# pcb7.net
KiCad netlist of a schematic drawn in EAGLE
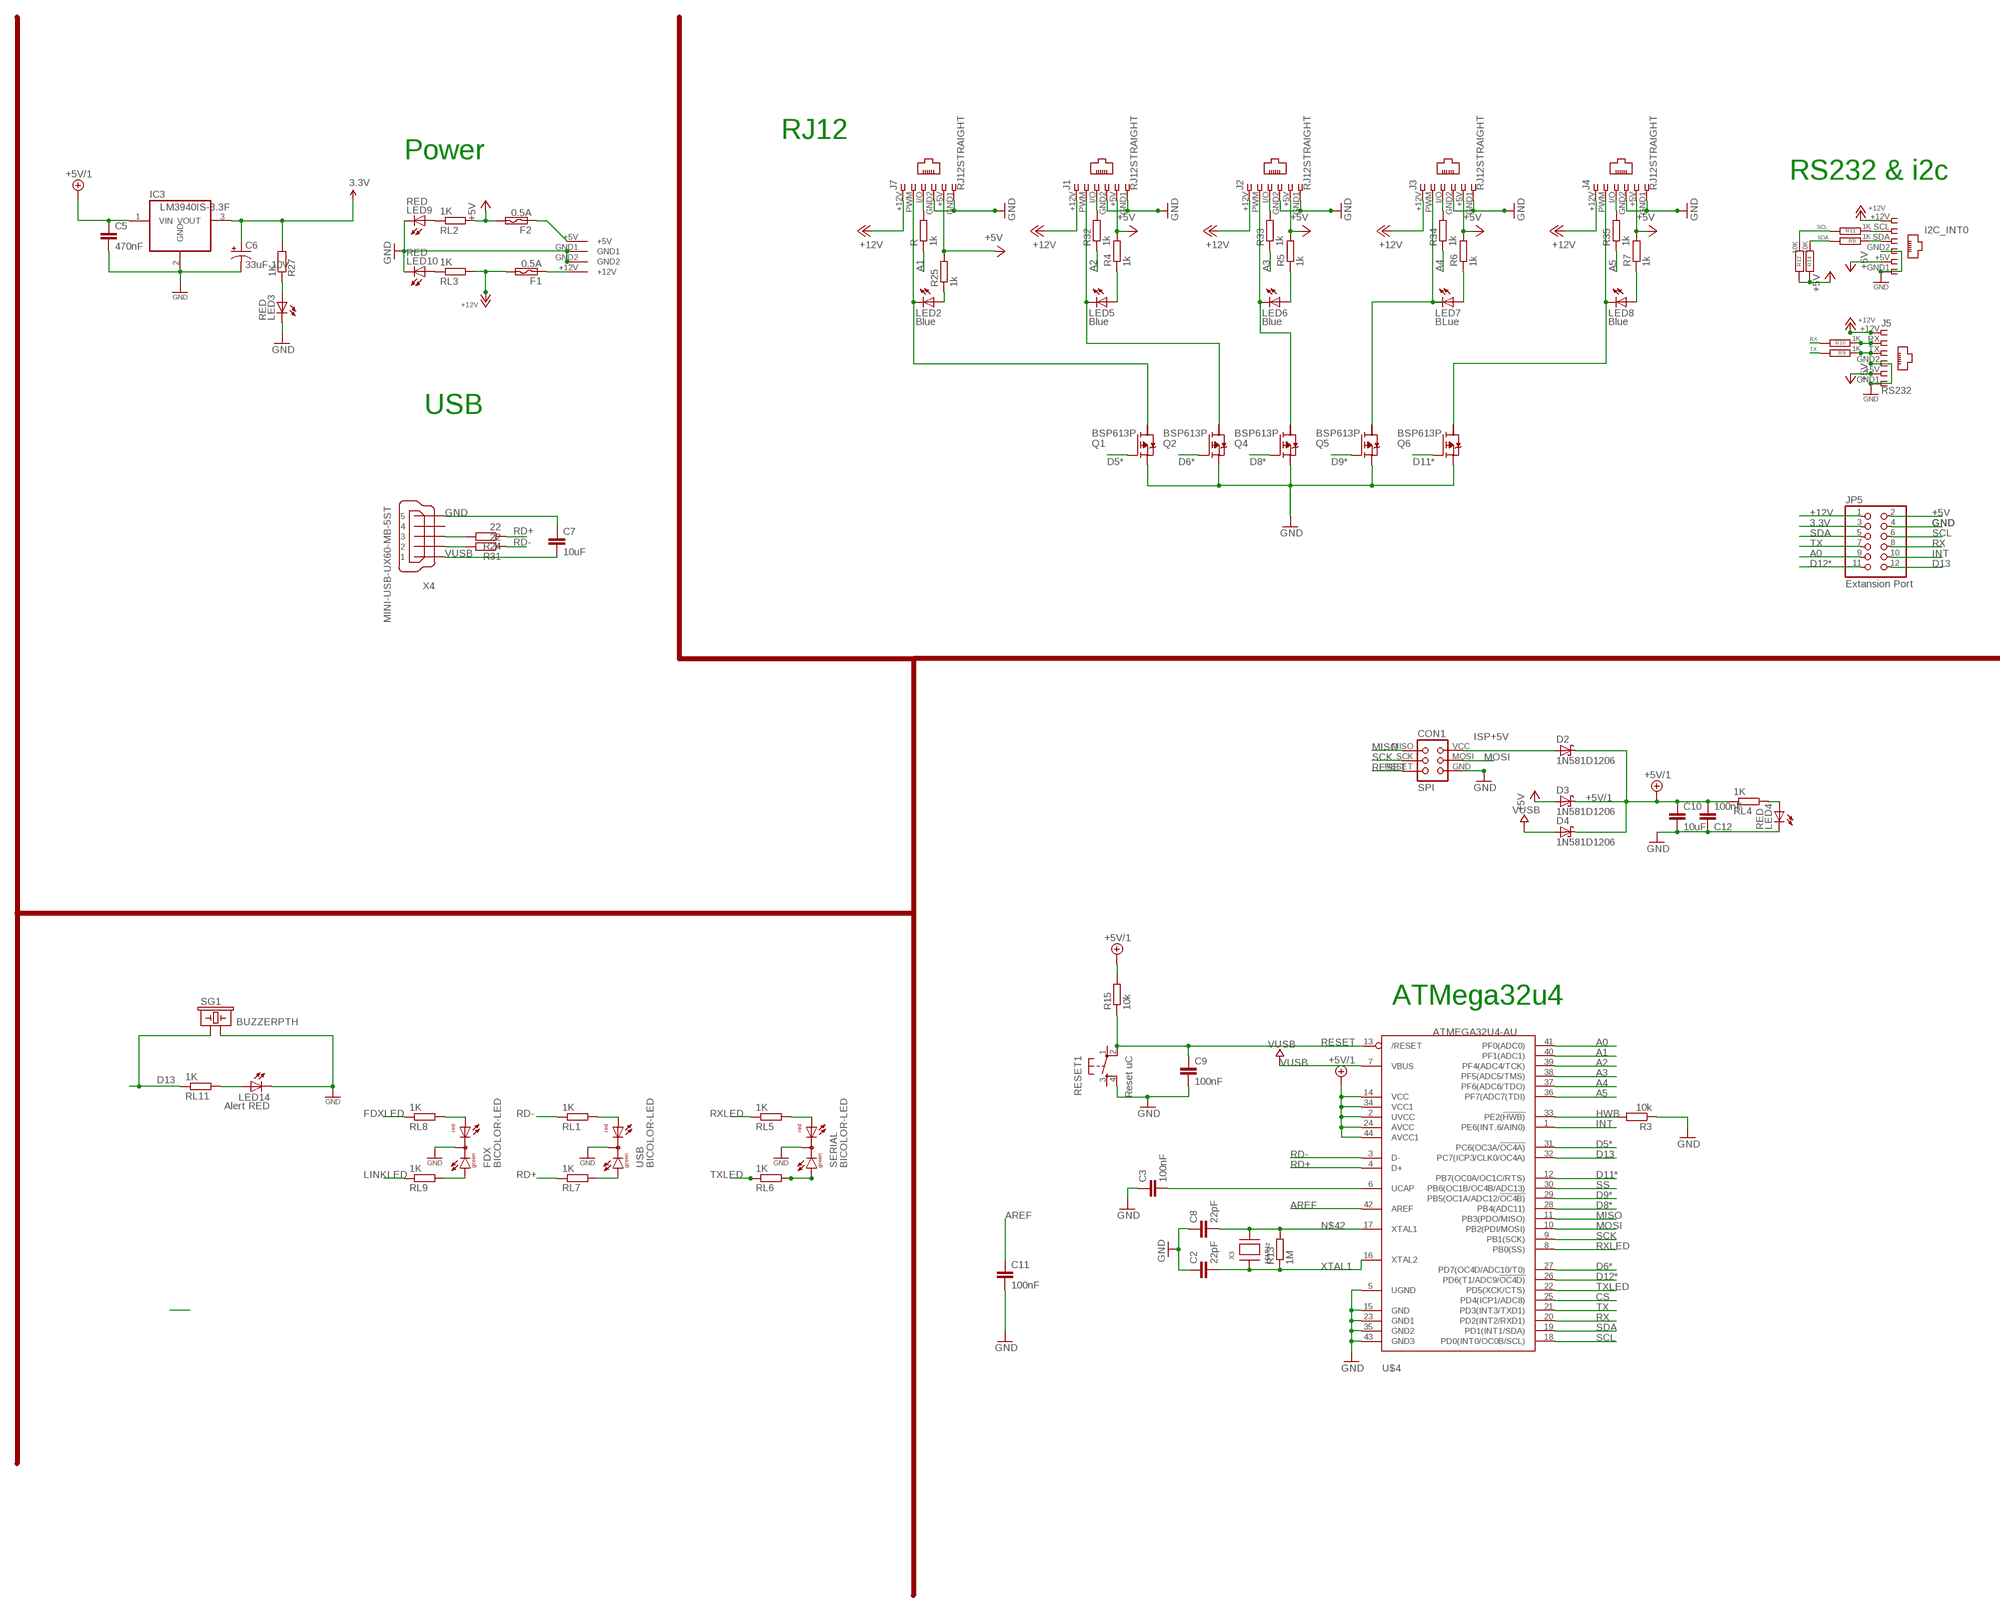
[diagram p0: schematic, sheet 1, part 1 of 2]
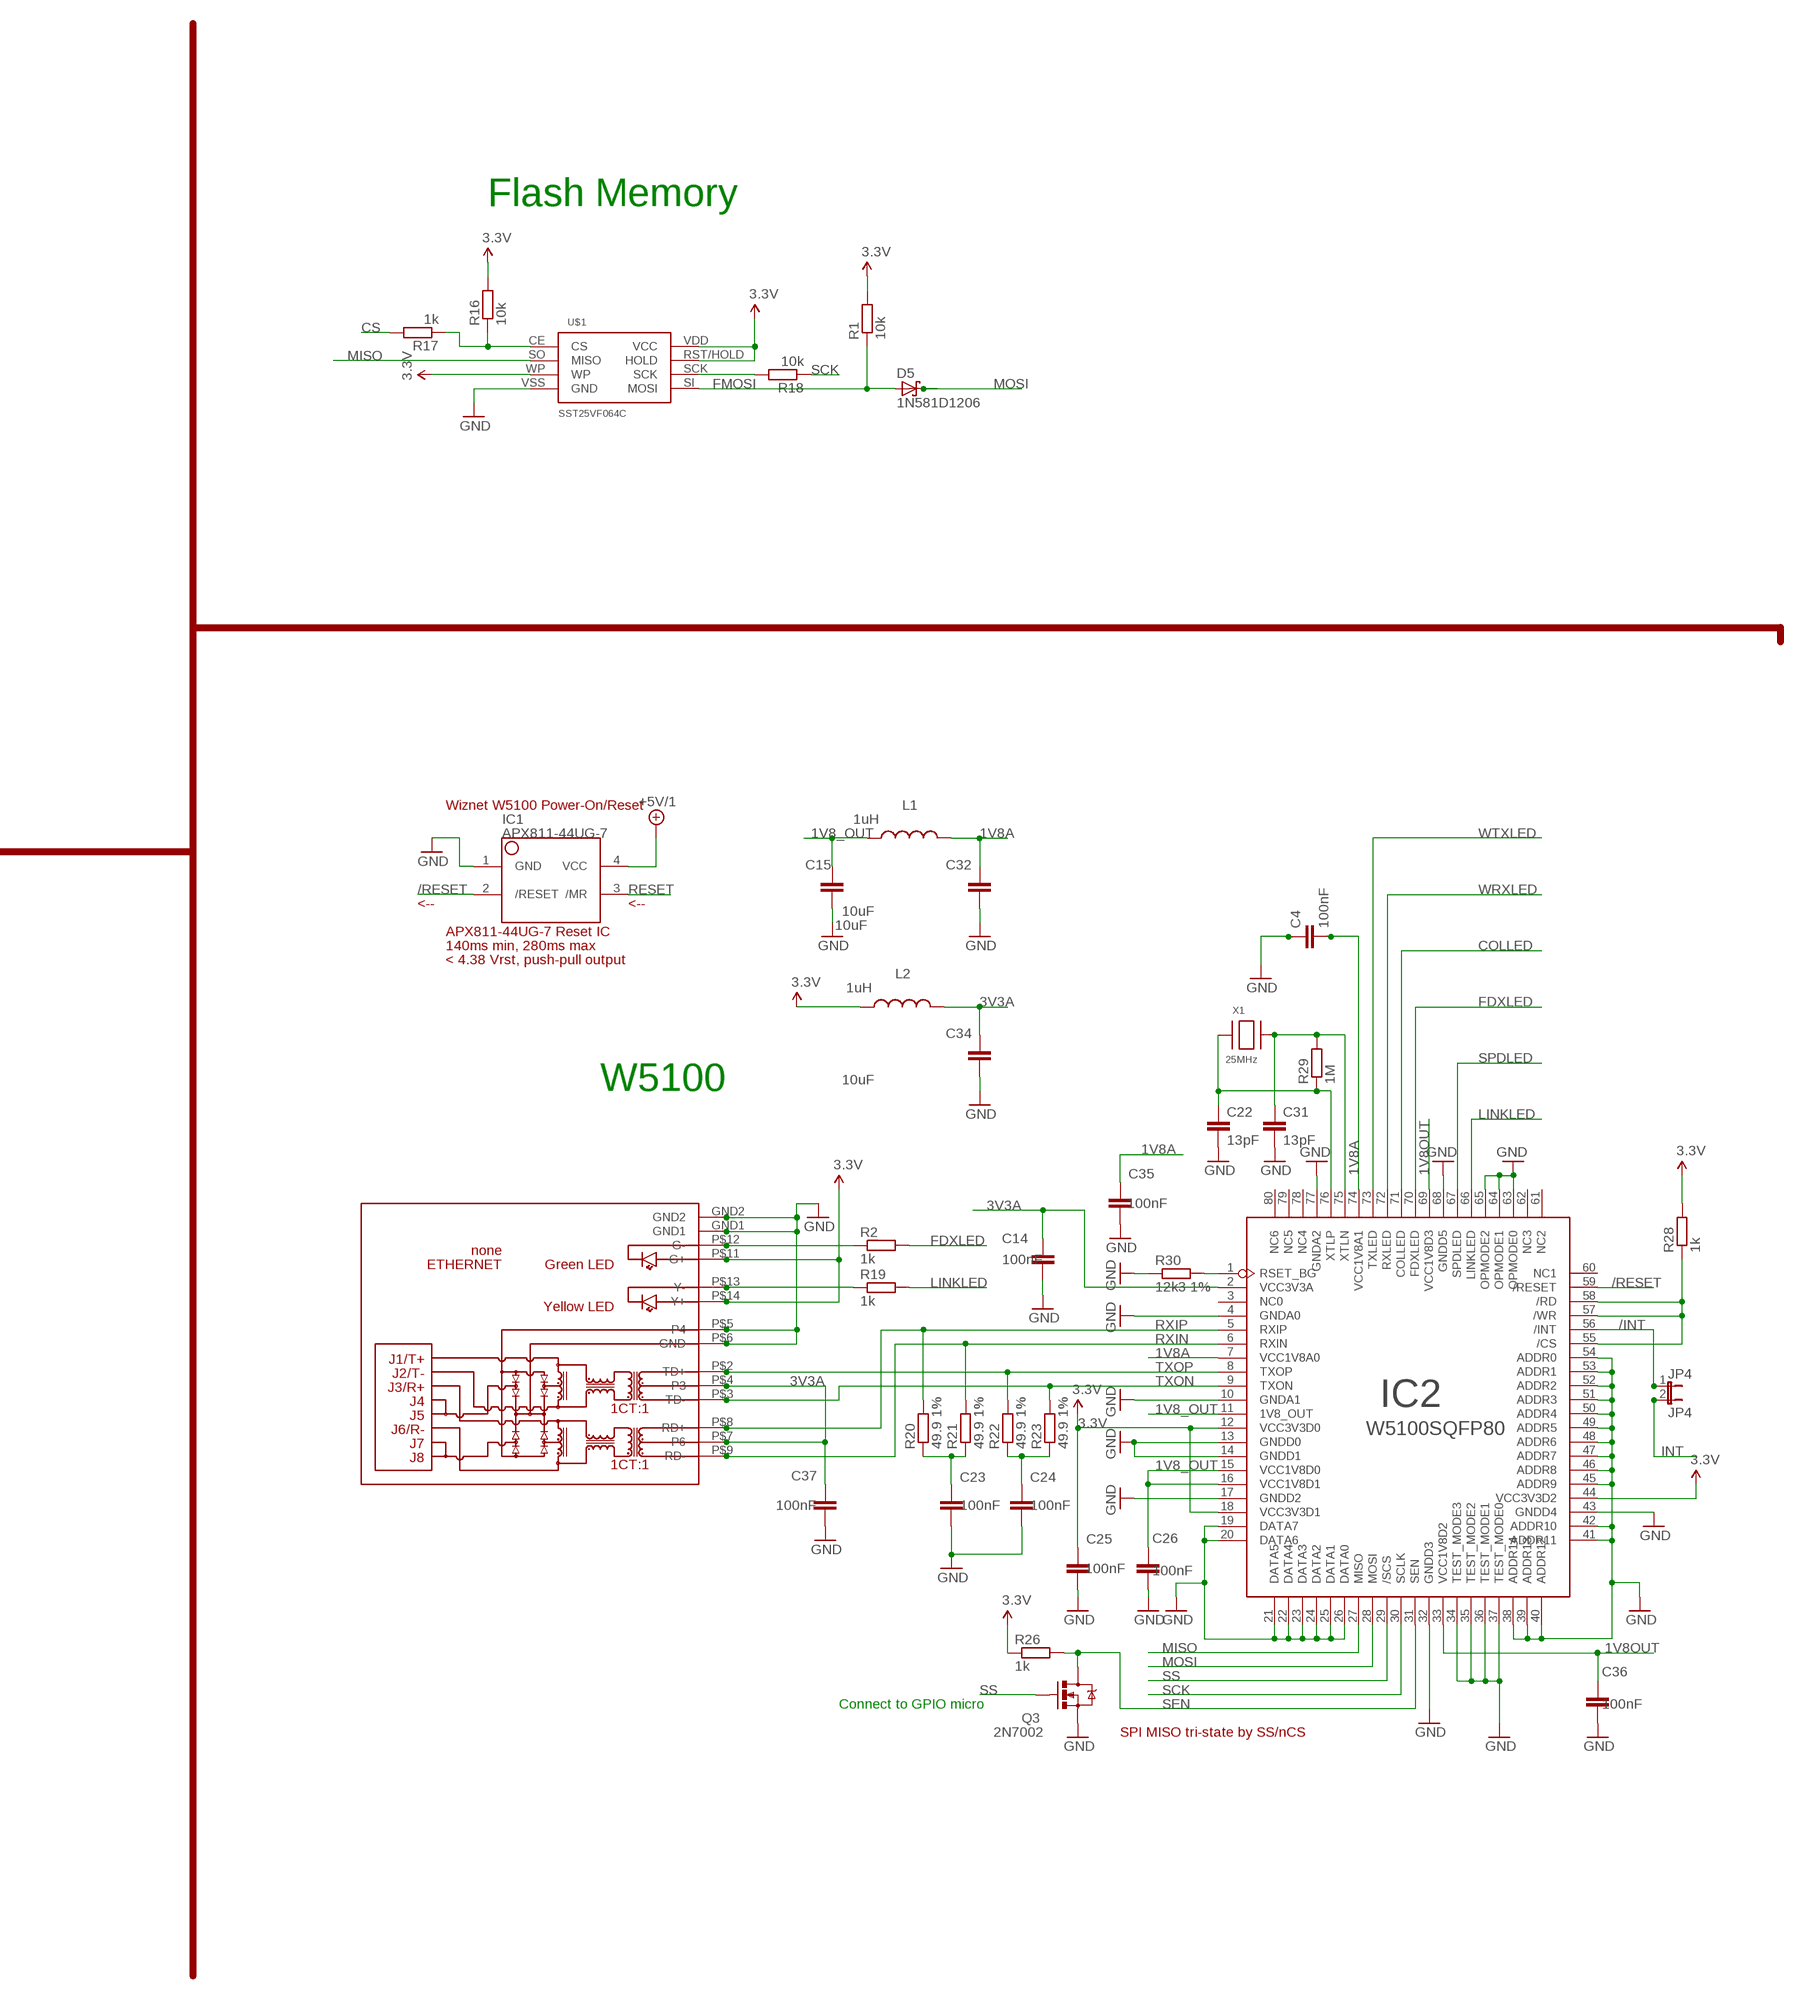
[diagram p1: schematic, sheet 1, part 2 of 2]

(export (version "E")
  (design (tool "Eeschema 10.0.6"))
  (components
    (comp (ref "C2")
      (value "22pF")
      (footprint "eagle-import:C1206")
      (libsource (lib "eagle-import") (part "C-EUC1206"))
    )
    (comp (ref "C3")
      (value "100nF")
      (footprint "eagle-import:C1206")
      (libsource (lib "eagle-import") (part "C-EUC1206"))
    )
    (comp (ref "C4")
      (value "100nF")
      (footprint "eagle-import:C1206")
      (libsource (lib "eagle-import") (part "C-EUC1206"))
    )
    (comp (ref "C5")
      (value "470nF")
      (footprint "eagle-import:C1206")
      (libsource (lib "eagle-import") (part "C-EUC1206"))
    )
    (comp (ref "C6")
      (value "33uF 10V")
      (footprint "eagle-import:EIA7343")
      (libsource (lib "eagle-import") (part "CAP_POL7343"))
    )
    (comp (ref "C7")
      (value "10uF")
      (footprint "eagle-import:C1206")
      (libsource (lib "eagle-import") (part "C-EUC1206"))
    )
    (comp (ref "C8")
      (value "22pF")
      (footprint "eagle-import:C1206")
      (libsource (lib "eagle-import") (part "C-EUC1206"))
    )
    (comp (ref "C9")
      (value "100nF")
      (footprint "eagle-import:C1206")
      (libsource (lib "eagle-import") (part "C-EUC1206"))
    )
    (comp (ref "C10")
      (value "10uF")
      (footprint "eagle-import:C1206")
      (libsource (lib "eagle-import") (part "C-EUC1206"))
    )
    (comp (ref "C11")
      (value "100nF")
      (footprint "eagle-import:C1206")
      (libsource (lib "eagle-import") (part "C-EUC1206"))
    )
    (comp (ref "C12")
      (value "100nF")
      (footprint "eagle-import:C1206")
      (libsource (lib "eagle-import") (part "C-EUC1206"))
    )
    (comp (ref "C14")
      (value "100nF")
      (footprint "eagle-import:C1206")
      (libsource (lib "eagle-import") (part "C-EUC1206"))
    )
    (comp (ref "C15")
      (value "10uF")
      (footprint "eagle-import:C1206")
      (libsource (lib "eagle-import") (part "C-EUC1206"))
    )
    (comp (ref "C22")
      (value "13pF")
      (footprint "eagle-import:C1206")
      (libsource (lib "eagle-import") (part "C-EUC1206"))
    )
    (comp (ref "C23")
      (value "100nF")
      (footprint "eagle-import:C1206")
      (libsource (lib "eagle-import") (part "C-EUC1206"))
    )
    (comp (ref "C24")
      (value "100nF")
      (footprint "eagle-import:C1206")
      (libsource (lib "eagle-import") (part "C-EUC1206"))
    )
    (comp (ref "C25")
      (value "100nF")
      (footprint "eagle-import:C1206")
      (libsource (lib "eagle-import") (part "C-EUC1206"))
    )
    (comp (ref "C26")
      (value "100nF")
      (footprint "eagle-import:C1206")
      (libsource (lib "eagle-import") (part "C-EUC1206"))
    )
    (comp (ref "C31")
      (value "13pF")
      (footprint "eagle-import:C1206")
      (libsource (lib "eagle-import") (part "C-EUC1206"))
    )
    (comp (ref "C32")
      (value "10uF")
      (footprint "eagle-import:C1206")
      (libsource (lib "eagle-import") (part "C-EUC1206"))
    )
    (comp (ref "C34")
      (value "10uF")
      (footprint "eagle-import:C1206")
      (libsource (lib "eagle-import") (part "C-EUC1206"))
    )
    (comp (ref "C35")
      (value "100nF")
      (footprint "eagle-import:C1206")
      (libsource (lib "eagle-import") (part "C-EUC1206"))
    )
    (comp (ref "C36")
      (value "100nF")
      (footprint "eagle-import:C1206")
      (libsource (lib "eagle-import") (part "C-EUC1206"))
    )
    (comp (ref "C37")
      (value "100nF")
      (footprint "eagle-import:C1206")
      (libsource (lib "eagle-import") (part "C-EUC1206"))
    )
    (comp (ref "CON1")
      (value "SPI")
      (footprint "eagle-import:TINYISP")
      (libsource (lib "eagle-import") (part "TINYISP"))
    )
    (comp (ref "D2")
      (value "1N581D1206")
      (footprint "eagle-import:LED-1206")
      (libsource (lib "eagle-import") (part "1N581D1206"))
    )
    (comp (ref "D3")
      (value "1N581D1206")
      (footprint "eagle-import:LED-1206")
      (libsource (lib "eagle-import") (part "1N581D1206"))
    )
    (comp (ref "D4")
      (value "1N581D1206")
      (footprint "eagle-import:LED-1206")
      (libsource (lib "eagle-import") (part "1N581D1206"))
    )
    (comp (ref "D5")
      (value "1N581D1206")
      (footprint "eagle-import:LED-1206")
      (libsource (lib "eagle-import") (part "1N581D1206"))
    )
    (comp (ref "ETHERNET")
      (value "none")
      (footprint "eagle-import:HY931147C")
      (libsource (lib "eagle-import") (part "HY911103AHY911103A"))
    )
    (comp (ref "F1")
      (value "0.5A")
      (footprint "eagle-import:C1812")
      (libsource (lib "eagle-import") (part "POLYSWITCHSMD1812"))
    )
    (comp (ref "F2")
      (value "0.5A")
      (footprint "eagle-import:C1812")
      (libsource (lib "eagle-import") (part "POLYSWITCHSMD1812"))
    )
    (comp (ref "FDX")
      (value "BICOLOR-LED")
      (footprint "eagle-import:BICOLOR-3MM")
      (libsource (lib "eagle-import") (part "BICOLOR-LED"))
    )
    (comp (ref "I2C_INT0")
      (value "I2C")
      (footprint "eagle-import:RJ12-STRAIGHT-I2C")
      (libsource (lib "eagle-import") (part "RJ12STRAIGHT-I2C"))
    )
    (comp (ref "IC1")
      (value "APX811-44UG-7")
      (footprint "eagle-import:SOT143-R")
      (libsource (lib "eagle-import") (part "APX81X-RESET-IC"))
    )
    (comp (ref "IC2")
      (value "W5100SQFP80")
      (footprint "eagle-import:SQFP80")
      (libsource (lib "eagle-import") (part "W5100SQFP80"))
    )
    (comp (ref "IC3")
      (value "LM3940IS-3.3F")
      (footprint "eagle-import:DD-3")
      (fields (field (name "MF") "TEXAS INSTRUMENTS") (field (name "MPN") "REG1117FAKTTT"))
      (libsource (lib "eagle-import") (part "LM3940IS-3.3F"))
    )
    (comp (ref "J1")
      (value "RJ12STRAIGHT")
      (footprint "eagle-import:RJ12-STRAIGHT")
      (libsource (lib "eagle-import") (part "RJ12STRAIGHT"))
    )
    (comp (ref "J2")
      (value "RJ12STRAIGHT")
      (footprint "eagle-import:RJ12-STRAIGHT")
      (libsource (lib "eagle-import") (part "RJ12STRAIGHT"))
    )
    (comp (ref "J3")
      (value "RJ12STRAIGHT")
      (footprint "eagle-import:RJ12-STRAIGHT")
      (libsource (lib "eagle-import") (part "RJ12STRAIGHT"))
    )
    (comp (ref "J4")
      (value "RJ12STRAIGHT")
      (footprint "eagle-import:RJ12-STRAIGHT")
      (libsource (lib "eagle-import") (part "RJ12STRAIGHT"))
    )
    (comp (ref "J5")
      (value "RS232")
      (footprint "eagle-import:RJ12-STRAIGHT-RS232")
      (libsource (lib "eagle-import") (part "RJ12STRAIGHT-RS232-SERVER"))
    )
    (comp (ref "J7")
      (value "RJ12STRAIGHT")
      (footprint "eagle-import:RJ12-STRAIGHT")
      (libsource (lib "eagle-import") (part "RJ12STRAIGHT"))
    )
    (comp (ref "JP4")
      (value "JP4")
      (footprint "eagle-import:1X02")
      (libsource (lib "eagle-import") (part "JUMPER-2PTH"))
    )
    (comp (ref "JP5")
      (value "Extansion Port")
      (footprint "eagle-import:2X06")
      (libsource (lib "eagle-import") (part "PINHD-2X6"))
    )
    (comp (ref "L1")
      (value "1uH")
      (footprint "eagle-import:L2012C")
      (libsource (lib "eagle-import") (part "L-USL2012C"))
    )
    (comp (ref "L2")
      (value "1uH")
      (footprint "eagle-import:L2012C")
      (libsource (lib "eagle-import") (part "L-USL2012C"))
    )
    (comp (ref "LED2")
      (value "Blue")
      (footprint "eagle-import:LED3MM")
      (libsource (lib "eagle-import") (part "LED3MM"))
    )
    (comp (ref "LED3")
      (value "RED")
      (footprint "eagle-import:LED3MM")
      (libsource (lib "eagle-import") (part "LED3MM"))
    )
    (comp (ref "LED4")
      (value "RED")
      (footprint "eagle-import:LED3MM")
      (libsource (lib "eagle-import") (part "LED3MM"))
    )
    (comp (ref "LED5")
      (value "Blue")
      (footprint "eagle-import:LED3MM")
      (libsource (lib "eagle-import") (part "LED3MM"))
    )
    (comp (ref "LED6")
      (value "Blue")
      (footprint "eagle-import:LED3MM")
      (libsource (lib "eagle-import") (part "LED3MM"))
    )
    (comp (ref "LED7")
      (value "BLue")
      (footprint "eagle-import:LED3MM")
      (libsource (lib "eagle-import") (part "LED3MM"))
    )
    (comp (ref "LED8")
      (value "Blue")
      (footprint "eagle-import:LED3MM")
      (libsource (lib "eagle-import") (part "LED3MM"))
    )
    (comp (ref "LED9")
      (value "RED")
      (footprint "eagle-import:LED3MM")
      (libsource (lib "eagle-import") (part "LED3MM"))
    )
    (comp (ref "LED10")
      (value "RED")
      (footprint "eagle-import:LED3MM")
      (libsource (lib "eagle-import") (part "LED3MM"))
    )
    (comp (ref "LED14")
      (value "Alert RED")
      (footprint "eagle-import:LED3MM")
      (libsource (lib "eagle-import") (part "LED3MM"))
    )
    (comp (ref "Q1")
      (value "BSP613P")
      (footprint "eagle-import:PG-SOT-223")
      (libsource (lib "eagle-import") (part "BSP613P"))
    )
    (comp (ref "Q2")
      (value "BSP613P")
      (footprint "eagle-import:PG-SOT-223")
      (libsource (lib "eagle-import") (part "BSP613P"))
    )
    (comp (ref "Q3")
      (value "2N7002")
      (footprint "eagle-import:SOT23-3")
      (libsource (lib "eagle-import") (part "MOSFET-NCHANNELSMD"))
    )
    (comp (ref "Q4")
      (value "BSP613P")
      (footprint "eagle-import:PG-SOT-223")
      (libsource (lib "eagle-import") (part "BSP613P"))
    )
    (comp (ref "Q5")
      (value "BSP613P")
      (footprint "eagle-import:PG-SOT-223")
      (libsource (lib "eagle-import") (part "BSP613P"))
    )
    (comp (ref "Q6")
      (value "BSP613P")
      (footprint "eagle-import:PG-SOT-223")
      (libsource (lib "eagle-import") (part "BSP613P"))
    )
    (comp (ref "R")
      (value "1k")
      (footprint "eagle-import:R0805")
      (libsource (lib "eagle-import") (part "R-EU_R0805"))
    )
    (comp (ref "R1")
      (value "10k")
      (footprint "eagle-import:R1206")
      (libsource (lib "eagle-import") (part "R-EU_R1206"))
    )
    (comp (ref "R2")
      (value "1k")
      (footprint "eagle-import:R0805")
      (libsource (lib "eagle-import") (part "R-EU_R0805"))
    )
    (comp (ref "R3")
      (value "10k")
      (footprint "eagle-import:R1206")
      (libsource (lib "eagle-import") (part "R-EU_R1206"))
    )
    (comp (ref "R4")
      (value "1k")
      (footprint "eagle-import:R0805")
      (libsource (lib "eagle-import") (part "R-EU_R0805"))
    )
    (comp (ref "R5")
      (value "1k")
      (footprint "eagle-import:R0805")
      (libsource (lib "eagle-import") (part "R-EU_R0805"))
    )
    (comp (ref "R6")
      (value "1k")
      (footprint "eagle-import:R0805")
      (libsource (lib "eagle-import") (part "R-EU_R0805"))
    )
    (comp (ref "R7")
      (value "1k")
      (footprint "eagle-import:R0805")
      (libsource (lib "eagle-import") (part "R-EU_R0805"))
    )
    (comp (ref "R8")
      (value "1K")
      (footprint "eagle-import:R0805")
      (libsource (lib "eagle-import") (part "R-EU_R0805"))
    )
    (comp (ref "R9")
      (value "1K")
      (footprint "eagle-import:R0805")
      (libsource (lib "eagle-import") (part "R-EU_R0805"))
    )
    (comp (ref "R10")
      (value "1K")
      (footprint "eagle-import:R0805")
      (libsource (lib "eagle-import") (part "R-EU_R0805"))
    )
    (comp (ref "R11")
      (value "1K")
      (footprint "eagle-import:R0805")
      (libsource (lib "eagle-import") (part "R-EU_R0805"))
    )
    (comp (ref "R12")
      (value "10K")
      (footprint "eagle-import:R1206")
      (libsource (lib "eagle-import") (part "R-EU_R1206"))
    )
    (comp (ref "R13")
      (value "1M")
      (footprint "eagle-import:R1206")
      (libsource (lib "eagle-import") (part "R-EU_R1206"))
    )
    (comp (ref "R14")
      (value "10K")
      (footprint "eagle-import:R1206")
      (libsource (lib "eagle-import") (part "R-EU_R1206"))
    )
    (comp (ref "R15")
      (value "10k")
      (footprint "eagle-import:R1206")
      (libsource (lib "eagle-import") (part "R-EU_R1206"))
    )
    (comp (ref "R16")
      (value "10k")
      (footprint "eagle-import:R1206")
      (libsource (lib "eagle-import") (part "R-EU_R1206"))
    )
    (comp (ref "R17")
      (value "1k")
      (footprint "eagle-import:R0805")
      (libsource (lib "eagle-import") (part "R-EU_R0805"))
    )
    (comp (ref "R18")
      (value "10k")
      (footprint "eagle-import:R1206")
      (libsource (lib "eagle-import") (part "R-EU_R1206"))
    )
    (comp (ref "R19")
      (value "1k")
      (footprint "eagle-import:R0805")
      (libsource (lib "eagle-import") (part "R-EU_R0805"))
    )
    (comp (ref "R20")
      (value "49.9 1%")
      (footprint "eagle-import:R0805W")
      (libsource (lib "eagle-import") (part "R-EU_R0805W"))
    )
    (comp (ref "R21")
      (value "49.9 1%")
      (footprint "eagle-import:R0805W")
      (libsource (lib "eagle-import") (part "R-EU_R0805W"))
    )
    (comp (ref "R22")
      (value "49.9 1%")
      (footprint "eagle-import:R0805W")
      (libsource (lib "eagle-import") (part "R-EU_R0805W"))
    )
    (comp (ref "R23")
      (value "49.9 1%")
      (footprint "eagle-import:R0805W")
      (libsource (lib "eagle-import") (part "R-EU_R0805W"))
    )
    (comp (ref "R24")
      (value "22")
      (footprint "eagle-import:M1206")
      (libsource (lib "eagle-import") (part "resistor_R-EU_M1206"))
    )
    (comp (ref "R25")
      (value "1k")
      (footprint "eagle-import:R0805")
      (libsource (lib "eagle-import") (part "R-EU_R0805"))
    )
    (comp (ref "R26")
      (value "1k")
      (footprint "eagle-import:R0805")
      (libsource (lib "eagle-import") (part "R-EU_R0805"))
    )
    (comp (ref "R27")
      (value "1K")
      (footprint "eagle-import:R0805")
      (libsource (lib "eagle-import") (part "R-EU_R0805"))
    )
    (comp (ref "R28")
      (value "1k")
      (footprint "eagle-import:R0805")
      (libsource (lib "eagle-import") (part "R-EU_R0805"))
    )
    (comp (ref "R29")
      (value "1M")
      (footprint "eagle-import:R1206")
      (libsource (lib "eagle-import") (part "R-EU_R1206"))
    )
    (comp (ref "R30")
      (value "12k3 1%")
      (footprint "eagle-import:R0805W")
      (libsource (lib "eagle-import") (part "R-EU_R0805W"))
    )
    (comp (ref "R31")
      (value "22")
      (footprint "eagle-import:M1206")
      (libsource (lib "eagle-import") (part "resistor_R-EU_M1206"))
    )
    (comp (ref "R32")
      (value "1k")
      (footprint "eagle-import:R0805")
      (libsource (lib "eagle-import") (part "R-EU_R0805"))
    )
    (comp (ref "R33")
      (value "1k")
      (footprint "eagle-import:R0805")
      (libsource (lib "eagle-import") (part "R-EU_R0805"))
    )
    (comp (ref "R34")
      (value "1k")
      (footprint "eagle-import:R0805")
      (libsource (lib "eagle-import") (part "R-EU_R0805"))
    )
    (comp (ref "R35")
      (value "1k")
      (footprint "eagle-import:R0805")
      (libsource (lib "eagle-import") (part "R-EU_R0805"))
    )
    (comp (ref "RESET1")
      (value "Reset uC")
      (footprint "eagle-import:TACTILE_SWITCH_SMD")
      (libsource (lib "eagle-import") (part "TAC_SWITCHSMD"))
    )
    (comp (ref "RL1")
      (value "1K")
      (footprint "eagle-import:R0805")
      (libsource (lib "eagle-import") (part "R-EU_R0805"))
    )
    (comp (ref "RL2")
      (value "1K")
      (footprint "eagle-import:R0805")
      (libsource (lib "eagle-import") (part "R-EU_R0805"))
    )
    (comp (ref "RL3")
      (value "1K")
      (footprint "eagle-import:R0805")
      (libsource (lib "eagle-import") (part "R-EU_R0805"))
    )
    (comp (ref "RL4")
      (value "1K")
      (footprint "eagle-import:R0805@1")
      (libsource (lib "eagle-import") (part "resistor_R-EU_R0805"))
    )
    (comp (ref "RL5")
      (value "1K")
      (footprint "eagle-import:R0805")
      (libsource (lib "eagle-import") (part "R-EU_R0805"))
    )
    (comp (ref "RL6")
      (value "1K")
      (footprint "eagle-import:R0805")
      (libsource (lib "eagle-import") (part "R-EU_R0805"))
    )
    (comp (ref "RL7")
      (value "1K")
      (footprint "eagle-import:R0805")
      (libsource (lib "eagle-import") (part "R-EU_R0805"))
    )
    (comp (ref "RL8")
      (value "1K")
      (footprint "eagle-import:R0805")
      (libsource (lib "eagle-import") (part "R-EU_R0805"))
    )
    (comp (ref "RL9")
      (value "1K")
      (footprint "eagle-import:R0805")
      (libsource (lib "eagle-import") (part "R-EU_R0805"))
    )
    (comp (ref "RL11")
      (value "1K")
      (footprint "eagle-import:R0805")
      (libsource (lib "eagle-import") (part "R-EU_R0805"))
    )
    (comp (ref "SERIAL")
      (value "BICOLOR-LED")
      (footprint "eagle-import:BICOLOR-3MM")
      (libsource (lib "eagle-import") (part "BICOLOR-LED"))
    )
    (comp (ref "SG1")
      (value "BUZZERPTH")
      (footprint "eagle-import:BUZZER-12MM")
      (libsource (lib "eagle-import") (part "BUZZERPTH"))
    )
    (comp (ref "U$1")
      (value "SST25VF064C")
      (footprint "eagle-import:SOIC_8-LEAD")
      (libsource (lib "eagle-import") (part "SST25VF064C"))
    )
    (comp (ref "U$4")
      (value "ATMEGA32U4-AU")
      (footprint "eagle-import:TQFP44")
      (libsource (lib "eagle-import") (part "ATMEGA32U4-AU"))
    )
    (comp (ref "U$6")
      (value "KPJX-4S-S")
      (footprint "eagle-import:KPJX-4S-S")
      (libsource (lib "eagle-import") (part "KPJX-4S-S"))
    )
    (comp (ref "USB")
      (value "BICOLOR-LED")
      (footprint "eagle-import:BICOLOR-3MM")
      (libsource (lib "eagle-import") (part "BICOLOR-LED"))
    )
    (comp (ref "X1")
      (value "25MHz")
      (footprint "eagle-import:NX6035")
      (libsource (lib "eagle-import") (part "XTALNX6035"))
    )
    (comp (ref "X3")
      (value "16MHz")
      (footprint "eagle-import:NX6035")
      (libsource (lib "eagle-import") (part "XTALNX6035"))
    )
    (comp (ref "X4")
      (value "MINI-USB-UX60-MB-5ST")
      (footprint "eagle-import:UX60-MB-5ST")
      (libsource (lib "eagle-import") (part "MINI-USB-UX60-MB-5ST"))
    )
  )
  (nets
    (net (code "1") (name "+5V") (class "Default")
      (node (ref "D3") (pin "A") (pinfunction "A_A") (pintype "passive"))
      (node (ref "F2") (pin "2") (pinfunction "2_2") (pintype "passive"))
      (node (ref "I2C_INT0") (pin "+5V") (pinfunction "5_+5V") (pintype "power_in"))
      (node (ref "J1") (pin "+5V") (pinfunction "5_+5V") (pintype "power_in"))
      (node (ref "J2") (pin "+5V") (pinfunction "5_+5V") (pintype "power_in"))
      (node (ref "J3") (pin "+5V") (pinfunction "5_+5V") (pintype "power_in"))
      (node (ref "J4") (pin "+5V") (pinfunction "5_+5V") (pintype "power_in"))
      (node (ref "J5") (pin "+5V") (pinfunction "5_+5V") (pintype "power_in"))
      (node (ref "J7") (pin "+5V") (pinfunction "5_+5V") (pintype "power_in"))
      (node (ref "JP5") (pin "2") (pinfunction "2_2") (pintype "passive"))
      (node (ref "R12") (pin "2") (pinfunction "2_2") (pintype "passive"))
      (node (ref "R14") (pin "2") (pinfunction "2_2") (pintype "passive"))
      (node (ref "R25") (pin "2") (pinfunction "2_2") (pintype "passive"))
      (node (ref "R4") (pin "2") (pinfunction "2_2") (pintype "passive"))
      (node (ref "R5") (pin "2") (pinfunction "2_2") (pintype "passive"))
      (node (ref "R6") (pin "2") (pinfunction "2_2") (pintype "passive"))
      (node (ref "R7") (pin "2") (pinfunction "2_2") (pintype "passive"))
      (node (ref "RL2") (pin "2") (pinfunction "2_2") (pintype "passive"))
    )
    (net (code "2") (name "+5V{slash}1") (class "Default")
      (node (ref "C10") (pin "1") (pinfunction "1_1") (pintype "passive"))
      (node (ref "C12") (pin "2") (pinfunction "2_2") (pintype "passive"))
      (node (ref "C5") (pin "1") (pinfunction "1_1") (pintype "passive"))
      (node (ref "D2") (pin "C") (pinfunction "C_C") (pintype "passive"))
      (node (ref "D3") (pin "C") (pinfunction "C_C") (pintype "passive"))
      (node (ref "D4") (pin "C") (pinfunction "C_C") (pintype "passive"))
      (node (ref "IC1") (pin "4") (pinfunction "VCC_4") (pintype "power_in"))
      (node (ref "IC3") (pin "1") (pinfunction "VIN_1") (pintype "input"))
      (node (ref "R15") (pin "2") (pinfunction "2_2") (pintype "passive"))
      (node (ref "RL4") (pin "1") (pinfunction "1_1") (pintype "passive"))
      (node (ref "U$4") (pin "14") (pinfunction "VCC_14") (pintype "bidirectional"))
      (node (ref "U$4") (pin "2") (pinfunction "UVCC_2") (pintype "bidirectional"))
      (node (ref "U$4") (pin "24") (pinfunction "AVCC_24") (pintype "bidirectional"))
      (node (ref "U$4") (pin "34") (pinfunction "VCC1_34") (pintype "bidirectional"))
      (node (ref "U$4") (pin "44") (pinfunction "AVCC1_44") (pintype "bidirectional"))
    )
    (net (code "3") (name "+12V") (class "Default")
      (node (ref "F1") (pin "2") (pinfunction "2_2") (pintype "passive"))
      (node (ref "I2C_INT0") (pin "+12V") (pinfunction "1_+12V") (pintype "power_in"))
      (node (ref "J1") (pin "+12V") (pinfunction "1_+12V") (pintype "power_in"))
      (node (ref "J2") (pin "+12V") (pinfunction "1_+12V") (pintype "power_in"))
      (node (ref "J3") (pin "+12V") (pinfunction "1_+12V") (pintype "power_in"))
      (node (ref "J4") (pin "+12V") (pinfunction "1_+12V") (pintype "power_in"))
      (node (ref "J5") (pin "+12V") (pinfunction "1_+12V") (pintype "power_in"))
      (node (ref "J7") (pin "+12V") (pinfunction "1_+12V") (pintype "power_in"))
      (node (ref "JP5") (pin "1") (pinfunction "1_1") (pintype "passive"))
      (node (ref "RL3") (pin "2") (pinfunction "2_2") (pintype "passive"))
    )
    (net (code "4") (name "/1V8A") (class "Default")
      (node (ref "C32") (pin "1") (pinfunction "1_1") (pintype "passive"))
      (node (ref "C35") (pin "1") (pinfunction "1_1") (pintype "passive"))
      (node (ref "C4") (pin "2") (pinfunction "2_2") (pintype "passive"))
      (node (ref "IC2") (pin "7") (pinfunction "VCC1V8A0_7") (pintype "bidirectional"))
      (node (ref "IC2") (pin "74") (pinfunction "VCC1V8A1_74") (pintype "bidirectional"))
      (node (ref "L1") (pin "2") (pinfunction "2_2") (pintype "passive"))
    )
    (net (code "5") (name "/1V8OUT") (class "Default")
      (node (ref "C36") (pin "1") (pinfunction "1_1") (pintype "passive"))
      (node (ref "IC2") (pin "33") (pinfunction "VCC1V8D2_33") (pintype "bidirectional"))
      (node (ref "IC2") (pin "69") (pinfunction "VCC1V8D3_69") (pintype "bidirectional"))
    )
    (net (code "6") (name "/1V8_OUT") (class "Default")
      (node (ref "C15") (pin "1") (pinfunction "1_1") (pintype "passive"))
      (node (ref "C26") (pin "1") (pinfunction "1_1") (pintype "passive"))
      (node (ref "IC2") (pin "11") (pinfunction "1V8_OUT_11") (pintype "bidirectional"))
      (node (ref "IC2") (pin "15") (pinfunction "VCC1V8D0_15") (pintype "bidirectional"))
      (node (ref "IC2") (pin "16") (pinfunction "VCC1V8D1_16") (pintype "bidirectional"))
      (node (ref "L1") (pin "1") (pinfunction "1_1") (pintype "passive"))
    )
    (net (code "7") (name "/3V3A") (class "Default")
      (node (ref "C14") (pin "1") (pinfunction "1_1") (pintype "passive"))
      (node (ref "C34") (pin "1") (pinfunction "1_1") (pintype "passive"))
      (node (ref "C37") (pin "1") (pinfunction "1_1") (pintype "passive"))
      (node (ref "ETHERNET") (pin "P$4") (pinfunction "P3_P$4") (pintype "bidirectional"))
      (node (ref "ETHERNET") (pin "P$7") (pinfunction "P6_P$7") (pintype "bidirectional"))
      (node (ref "IC2") (pin "2") (pinfunction "VCC3V3A_2") (pintype "bidirectional"))
      (node (ref "L2") (pin "2") (pinfunction "2_2") (pintype "passive"))
    )
    (net (code "8") (name "/A0") (class "Default")
      (node (ref "JP5") (pin "9") (pinfunction "9_9") (pintype "passive"))
      (node (ref "U$4") (pin "41") (pinfunction "PF0(ADC0)_41") (pintype "bidirectional"))
    )
    (net (code "9") (name "/A1") (class "Default")
      (node (ref "R") (pin "1") (pinfunction "1_1") (pintype "passive"))
      (node (ref "U$4") (pin "40") (pinfunction "PF1(ADC1)_40") (pintype "bidirectional"))
    )
    (net (code "10") (name "/A2") (class "Default")
      (node (ref "R32") (pin "1") (pinfunction "1_1") (pintype "passive"))
      (node (ref "U$4") (pin "39") (pinfunction "PF4(ADC4/TCK)_39") (pintype "bidirectional"))
    )
    (net (code "11") (name "/A3") (class "Default")
      (node (ref "R33") (pin "1") (pinfunction "1_1") (pintype "passive"))
      (node (ref "U$4") (pin "38") (pinfunction "PF5(ADC5/TMS)_38") (pintype "bidirectional"))
    )
    (net (code "12") (name "/A4") (class "Default")
      (node (ref "R34") (pin "1") (pinfunction "1_1") (pintype "passive"))
      (node (ref "U$4") (pin "37") (pinfunction "PF6(ADC6/TDO)_37") (pintype "bidirectional"))
    )
    (net (code "13") (name "/A5") (class "Default")
      (node (ref "R35") (pin "1") (pinfunction "1_1") (pintype "passive"))
      (node (ref "U$4") (pin "36") (pinfunction "PF7(ADC7(TDI)_36") (pintype "bidirectional"))
    )
    (net (code "14") (name "/AREF") (class "Default")
      (node (ref "C11") (pin "1") (pinfunction "1_1") (pintype "passive"))
      (node (ref "U$4") (pin "42") (pinfunction "AREF_42") (pintype "bidirectional"))
    )
    (net (code "15") (name "/COLLED") (class "Default")
      (node (ref "IC2") (pin "71") (pinfunction "COLLED_71") (pintype "bidirectional"))
    )
    (net (code "16") (name "/CS") (class "Default")
      (node (ref "R17") (pin "2") (pinfunction "2_2") (pintype "passive"))
      (node (ref "U$4") (pin "25") (pinfunction "PD4(ICP1/ADC8)_25") (pintype "bidirectional"))
    )
    (net (code "17") (name "/D5*") (class "Default")
      (node (ref "Q1") (pin "1") (pinfunction "G_1") (pintype "passive"))
      (node (ref "U$4") (pin "31") (pinfunction "PC6(OC3A/~{OC4A})_31") (pintype "bidirectional"))
    )
    (net (code "18") (name "/D6*") (class "Default")
      (node (ref "Q2") (pin "1") (pinfunction "G_1") (pintype "passive"))
      (node (ref "U$4") (pin "27") (pinfunction "PD7(OC4D/ADC10/T0)_27") (pintype "bidirectional"))
    )
    (net (code "19") (name "/D8*") (class "Default")
      (node (ref "Q4") (pin "1") (pinfunction "G_1") (pintype "passive"))
      (node (ref "U$4") (pin "28") (pinfunction "PB4(ADC11)_28") (pintype "bidirectional"))
    )
    (net (code "20") (name "/D9*") (class "Default")
      (node (ref "Q5") (pin "1") (pinfunction "G_1") (pintype "passive"))
      (node (ref "U$4") (pin "29") (pinfunction "PB5(OC1A/ADC12/~{OC4B})_29") (pintype "bidirectional"))
    )
    (net (code "21") (name "/D11*") (class "Default")
      (node (ref "Q6") (pin "1") (pinfunction "G_1") (pintype "passive"))
      (node (ref "U$4") (pin "12") (pinfunction "PB7(OC0A/OC1C/RTS)_12") (pintype "bidirectional"))
    )
    (net (code "22") (name "/D12*") (class "Default")
      (node (ref "JP5") (pin "11") (pinfunction "11_11") (pintype "passive"))
      (node (ref "U$4") (pin "26") (pinfunction "PD6(T1/ADC9/~{OC4D})_26") (pintype "bidirectional"))
    )
    (net (code "23") (name "/D13") (class "Default")
      (node (ref "JP5") (pin "12") (pinfunction "12_12") (pintype "passive"))
      (node (ref "RL11") (pin "1") (pinfunction "1_1") (pintype "passive"))
      (node (ref "SG1") (pin "+") (pinfunction "1_+") (pintype "passive"))
      (node (ref "U$4") (pin "32") (pinfunction "PC7(ICP3/CLK0/OC4A)_32") (pintype "bidirectional"))
    )
    (net (code "24") (name "/FDXLED") (class "Default")
      (node (ref "IC2") (pin "70") (pinfunction "FDXLED_70") (pintype "bidirectional"))
      (node (ref "R2") (pin "2") (pinfunction "2_2") (pintype "passive"))
      (node (ref "RL8") (pin "1") (pinfunction "1_1") (pintype "passive"))
    )
    (net (code "25") (name "/FMOSI") (class "Default")
      (node (ref "D5") (pin "A") (pinfunction "A_A") (pintype "passive"))
      (node (ref "R1") (pin "1") (pinfunction "1_1") (pintype "passive"))
      (node (ref "U$1") (pin "SI") (pinfunction "MOSI_SI") (pintype "bidirectional"))
    )
    (net (code "26") (name "/HWB") (class "Default")
      (node (ref "R3") (pin "2") (pinfunction "2_2") (pintype "passive"))
      (node (ref "U$4") (pin "33") (pinfunction "PE2(~{HWB})_33") (pintype "bidirectional"))
    )
    (net (code "27") (name "/INT") (class "Default")
      (node (ref "JP4") (pin "2") (pinfunction "2_2") (pintype "passive"))
      (node (ref "JP5") (pin "10") (pinfunction "10_10") (pintype "passive"))
      (node (ref "U$4") (pin "1") (pinfunction "PE6(INT.6/AIN0)_1") (pintype "bidirectional"))
    )
    (net (code "28") (name "/ISP+5V") (class "Default")
      (node (ref "CON1") (pin "VCC") (pinfunction "VCC_VCC") (pintype "passive"))
      (node (ref "D2") (pin "A") (pinfunction "A_A") (pintype "passive"))
    )
    (net (code "29") (name "/LINKLED") (class "Default")
      (node (ref "IC2") (pin "66") (pinfunction "LINKLED_66") (pintype "bidirectional"))
      (node (ref "R19") (pin "2") (pinfunction "2_2") (pintype "passive"))
      (node (ref "RL9") (pin "1") (pinfunction "1_1") (pintype "passive"))
    )
    (net (code "30") (name "/MISO") (class "Default")
      (node (ref "CON1") (pin "MISO") (pinfunction "MISO_MISO") (pintype "passive"))
      (node (ref "IC2") (pin "27") (pinfunction "MISO_27") (pintype "bidirectional"))
      (node (ref "U$1") (pin "SO") (pinfunction "MISO_SO") (pintype "bidirectional"))
      (node (ref "U$4") (pin "11") (pinfunction "PB3(PDO/MISO)_11") (pintype "bidirectional"))
    )
    (net (code "31") (name "/MOSI") (class "Default")
      (node (ref "CON1") (pin "MOSI") (pinfunction "MOSI_MOSI") (pintype "passive"))
      (node (ref "D5") (pin "C") (pinfunction "C_C") (pintype "passive"))
      (node (ref "IC2") (pin "28") (pinfunction "MOSI_28") (pintype "bidirectional"))
      (node (ref "U$4") (pin "10") (pinfunction "PB2(PDI/MOSI)_10") (pintype "bidirectional"))
    )
    (net (code "32") (name "/N$42") (class "Default")
      (node (ref "C8") (pin "2") (pinfunction "2_2") (pintype "passive"))
      (node (ref "R13") (pin "2") (pinfunction "2_2") (pintype "passive"))
      (node (ref "U$4") (pin "17") (pinfunction "XTAL1_17") (pintype "bidirectional"))
      (node (ref "X3") (pin "P$2") (pinfunction "P$2_P$2") (pintype "bidirectional"))
    )
    (net (code "33") (name "/RD+") (class "Default")
      (node (ref "R24") (pin "1") (pinfunction "1_1") (pintype "passive"))
      (node (ref "RL7") (pin "1") (pinfunction "1_1") (pintype "passive"))
      (node (ref "U$4") (pin "4") (pinfunction "D+_4") (pintype "bidirectional"))
    )
    (net (code "34") (name "/RD-") (class "Default")
      (node (ref "R31") (pin "1") (pinfunction "1_1") (pintype "passive"))
      (node (ref "RL1") (pin "1") (pinfunction "1_1") (pintype "passive"))
      (node (ref "U$4") (pin "3") (pinfunction "D-_3") (pintype "bidirectional"))
    )
    (net (code "35") (name "/RESET") (class "Default")
      (node (ref "C9") (pin "1") (pinfunction "1_1") (pintype "passive"))
      (node (ref "CON1") (pin "RESET") (pinfunction "RESET_RESET") (pintype "passive"))
      (node (ref "IC1") (pin "3") (pinfunction "/MR_3") (pintype "input"))
      (node (ref "R15") (pin "1") (pinfunction "1_1") (pintype "passive"))
      (node (ref "RESET1") (pin "2") (pinfunction "2_2") (pintype "passive"))
      (node (ref "U$4") (pin "13") (pinfunction "/RESET_13") (pintype "bidirectional"))
    )
    (net (code "36") (name "/RX") (class "Default")
      (node (ref "JP5") (pin "8") (pinfunction "8_8") (pintype "passive"))
      (node (ref "R10") (pin "2") (pinfunction "2_2") (pintype "passive"))
      (node (ref "U$4") (pin "20") (pinfunction "PD2(INT2/RXD1)_20") (pintype "bidirectional"))
    )
    (net (code "37") (name "/RXIN") (class "Default")
      (node (ref "ETHERNET") (pin "P$9") (pinfunction "RD-_P$9") (pintype "bidirectional"))
      (node (ref "IC2") (pin "6") (pinfunction "RXIN_6") (pintype "bidirectional"))
      (node (ref "R21") (pin "2") (pinfunction "2_2") (pintype "passive"))
    )
    (net (code "38") (name "/RXIP") (class "Default")
      (node (ref "ETHERNET") (pin "P$8") (pinfunction "RD+_P$8") (pintype "bidirectional"))
      (node (ref "IC2") (pin "5") (pinfunction "RXIP_5") (pintype "bidirectional"))
      (node (ref "R20") (pin "2") (pinfunction "2_2") (pintype "passive"))
    )
    (net (code "39") (name "/RXLED") (class "Default")
      (node (ref "RL5") (pin "1") (pinfunction "1_1") (pintype "passive"))
      (node (ref "U$4") (pin "8") (pinfunction "PB0(SS)_8") (pintype "bidirectional"))
    )
    (net (code "40") (name "/SCK") (class "Default")
      (node (ref "CON1") (pin "SCK") (pinfunction "SCK_SCK") (pintype "passive"))
      (node (ref "IC2") (pin "30") (pinfunction "SCLK_30") (pintype "bidirectional"))
      (node (ref "R18") (pin "1") (pinfunction "1_1") (pintype "passive"))
      (node (ref "U$4") (pin "9") (pinfunction "PB1(SCK)_9") (pintype "bidirectional"))
    )
    (net (code "41") (name "/SCL") (class "Default")
      (node (ref "JP5") (pin "6") (pinfunction "6_6") (pintype "passive"))
      (node (ref "R11") (pin "2") (pinfunction "2_2") (pintype "passive"))
      (node (ref "R12") (pin "1") (pinfunction "1_1") (pintype "passive"))
      (node (ref "U$4") (pin "18") (pinfunction "PD0(INT0/OC0B/SCL)_18") (pintype "bidirectional"))
    )
    (net (code "42") (name "/SDA") (class "Default")
      (node (ref "JP5") (pin "5") (pinfunction "5_5") (pintype "passive"))
      (node (ref "R14") (pin "1") (pinfunction "1_1") (pintype "passive"))
      (node (ref "R8") (pin "2") (pinfunction "2_2") (pintype "passive"))
      (node (ref "U$4") (pin "19") (pinfunction "PD1(INT1/SDA)_19") (pintype "bidirectional"))
    )
    (net (code "43") (name "/SEN") (class "Default")
      (node (ref "IC2") (pin "31") (pinfunction "SEN_31") (pintype "bidirectional"))
      (node (ref "Q3") (pin "3") (pinfunction "D_3") (pintype "passive"))
      (node (ref "R26") (pin "2") (pinfunction "2_2") (pintype "passive"))
    )
    (net (code "44") (name "/SPDLED") (class "Default")
      (node (ref "IC2") (pin "67") (pinfunction "SPDLED_67") (pintype "bidirectional"))
    )
    (net (code "45") (name "/SS") (class "Default")
      (node (ref "IC2") (pin "29") (pinfunction "/SCS_29") (pintype "bidirectional"))
      (node (ref "Q3") (pin "1") (pinfunction "G_1") (pintype "passive"))
      (node (ref "U$4") (pin "30") (pinfunction "PB6(OC1B/OC4B/ADC13)_30") (pintype "bidirectional"))
    )
    (net (code "46") (name "/TX") (class "Default")
      (node (ref "JP5") (pin "7") (pinfunction "7_7") (pintype "passive"))
      (node (ref "R9") (pin "2") (pinfunction "2_2") (pintype "passive"))
      (node (ref "U$4") (pin "21") (pinfunction "PD3(INT3/TXD1)_21") (pintype "bidirectional"))
    )
    (net (code "47") (name "/TXLED") (class "Default")
      (node (ref "RL6") (pin "1") (pinfunction "1_1") (pintype "passive"))
      (node (ref "U$4") (pin "22") (pinfunction "PD5(XCK/CTS)_22") (pintype "bidirectional"))
    )
    (net (code "48") (name "/TXON") (class "Default")
      (node (ref "ETHERNET") (pin "P$3") (pinfunction "TD-_P$3") (pintype "bidirectional"))
      (node (ref "IC2") (pin "9") (pinfunction "TXON_9") (pintype "bidirectional"))
      (node (ref "R23") (pin "2") (pinfunction "2_2") (pintype "passive"))
    )
    (net (code "49") (name "/TXOP") (class "Default")
      (node (ref "ETHERNET") (pin "P$2") (pinfunction "TD+_P$2") (pintype "bidirectional"))
      (node (ref "IC2") (pin "8") (pinfunction "TXOP_8") (pintype "bidirectional"))
      (node (ref "R22") (pin "2") (pinfunction "2_2") (pintype "passive"))
    )
    (net (code "50") (name "/WRXLED") (class "Default")
      (node (ref "IC2") (pin "72") (pinfunction "RXLED_72") (pintype "bidirectional"))
    )
    (net (code "51") (name "/WTXLED") (class "Default")
      (node (ref "IC2") (pin "73") (pinfunction "TXLED_73") (pintype "bidirectional"))
    )
    (net (code "52") (name "/XTAL1") (class "Default")
      (node (ref "C2") (pin "2") (pinfunction "2_2") (pintype "passive"))
      (node (ref "R13") (pin "1") (pinfunction "1_1") (pintype "passive"))
      (node (ref "U$4") (pin "16") (pinfunction "XTAL2_16") (pintype "bidirectional"))
      (node (ref "X3") (pin "P$1") (pinfunction "P$1_P$1") (pintype "bidirectional"))
    )
    (net (code "53") (name "/{slash}INT") (class "Default")
      (node (ref "IC2") (pin "56") (pinfunction "/INT_56") (pintype "bidirectional"))
      (node (ref "JP4") (pin "1") (pinfunction "1_1") (pintype "passive"))
    )
    (net (code "54") (name "/{slash}RESET") (class "Default")
      (node (ref "IC1") (pin "2") (pinfunction "/RESET_2") (pintype "output"))
      (node (ref "IC2") (pin "59") (pinfunction "/RESET_59") (pintype "bidirectional"))
    )
    (net (code "55") (name "3.3V") (class "Default")
      (node (ref "C25") (pin "1") (pinfunction "1_1") (pintype "passive"))
      (node (ref "C6") (pin "A") (pinfunction "+_A") (pintype "passive"))
      (node (ref "ETHERNET") (pin "P$11") (pinfunction "G+_P$11") (pintype "bidirectional"))
      (node (ref "ETHERNET") (pin "P$14") (pinfunction "Y+_P$14") (pintype "bidirectional"))
      (node (ref "IC2") (pin "12") (pinfunction "VCC3V3D0_12") (pintype "bidirectional"))
      (node (ref "IC2") (pin "18") (pinfunction "VCC3V3D1_18") (pintype "bidirectional"))
      (node (ref "IC2") (pin "44") (pinfunction "VCC3V3D2_44") (pintype "bidirectional"))
      (node (ref "IC3") (pin "3") (pinfunction "VOUT_3") (pintype "output"))
      (node (ref "JP5") (pin "3") (pinfunction "3_3") (pintype "passive"))
      (node (ref "L2") (pin "1") (pinfunction "1_1") (pintype "passive"))
      (node (ref "R1") (pin "2") (pinfunction "2_2") (pintype "passive"))
      (node (ref "R16") (pin "2") (pinfunction "2_2") (pintype "passive"))
      (node (ref "R26") (pin "1") (pinfunction "1_1") (pintype "passive"))
      (node (ref "R27") (pin "2") (pinfunction "2_2") (pintype "passive"))
      (node (ref "R28") (pin "2") (pinfunction "2_2") (pintype "passive"))
      (node (ref "U$1") (pin "RST/HOLD") (pinfunction "HOLD_RST/HOLD") (pintype "bidirectional"))
      (node (ref "U$1") (pin "VDD") (pinfunction "VCC_VDD") (pintype "bidirectional"))
      (node (ref "U$1") (pin "WP") (pinfunction "WP_WP") (pintype "bidirectional"))
    )
    (net (code "56") (name "GND") (class "Default")
      (node (ref "C10") (pin "2") (pinfunction "2_2") (pintype "passive"))
      (node (ref "C11") (pin "2") (pinfunction "2_2") (pintype "passive"))
      (node (ref "C12") (pin "1") (pinfunction "1_1") (pintype "passive"))
      (node (ref "C14") (pin "2") (pinfunction "2_2") (pintype "passive"))
      (node (ref "C15") (pin "2") (pinfunction "2_2") (pintype "passive"))
      (node (ref "C2") (pin "1") (pinfunction "1_1") (pintype "passive"))
      (node (ref "C22") (pin "2") (pinfunction "2_2") (pintype "passive"))
      (node (ref "C23") (pin "2") (pinfunction "2_2") (pintype "passive"))
      (node (ref "C24") (pin "2") (pinfunction "2_2") (pintype "passive"))
      (node (ref "C25") (pin "2") (pinfunction "2_2") (pintype "passive"))
      (node (ref "C26") (pin "2") (pinfunction "2_2") (pintype "passive"))
      (node (ref "C3") (pin "1") (pinfunction "1_1") (pintype "passive"))
      (node (ref "C31") (pin "2") (pinfunction "2_2") (pintype "passive"))
      (node (ref "C32") (pin "2") (pinfunction "2_2") (pintype "passive"))
      (node (ref "C34") (pin "2") (pinfunction "2_2") (pintype "passive"))
      (node (ref "C35") (pin "2") (pinfunction "2_2") (pintype "passive"))
      (node (ref "C36") (pin "2") (pinfunction "2_2") (pintype "passive"))
      (node (ref "C37") (pin "2") (pinfunction "2_2") (pintype "passive"))
      (node (ref "C4") (pin "1") (pinfunction "1_1") (pintype "passive"))
      (node (ref "C5") (pin "2") (pinfunction "2_2") (pintype "passive"))
      (node (ref "C6") (pin "C") (pinfunction "-_C") (pintype "passive"))
      (node (ref "C7") (pin "1") (pinfunction "1_1") (pintype "passive"))
      (node (ref "C8") (pin "1") (pinfunction "1_1") (pintype "passive"))
      (node (ref "C9") (pin "2") (pinfunction "2_2") (pintype "passive"))
      (node (ref "CON1") (pin "GND") (pinfunction "GND_GND") (pintype "passive"))
      (node (ref "ETHERNET") (pin "GND1") (pinfunction "GND1_GND1") (pintype "bidirectional"))
      (node (ref "ETHERNET") (pin "GND2") (pinfunction "GND2_GND2") (pintype "bidirectional"))
      (node (ref "ETHERNET") (pin "P$5") (pinfunction "P4_P$5") (pintype "bidirectional"))
      (node (ref "ETHERNET") (pin "P$6") (pinfunction "GND_P$6") (pintype "bidirectional"))
      (node (ref "FDX") (pin "2") (pinfunction "C_2") (pintype "passive"))
      (node (ref "I2C_INT0") (pin "GND1") (pinfunction "6_GND1") (pintype "power_in"))
      (node (ref "I2C_INT0") (pin "GND2") (pinfunction "4_GND2") (pintype "power_in"))
      (node (ref "IC1") (pin "1") (pinfunction "GND_1") (pintype "power_in"))
      (node (ref "IC2") (pin "10") (pinfunction "GNDA1_10") (pintype "bidirectional"))
      (node (ref "IC2") (pin "13") (pinfunction "GNDD0_13") (pintype "bidirectional"))
      (node (ref "IC2") (pin "14") (pinfunction "GNDD1_14") (pintype "bidirectional"))
      (node (ref "IC2") (pin "17") (pinfunction "GNDD2_17") (pintype "bidirectional"))
      (node (ref "IC2") (pin "19") (pinfunction "DATA7_19") (pintype "bidirectional"))
      (node (ref "IC2") (pin "20") (pinfunction "DATA6_20") (pintype "bidirectional"))
      (node (ref "IC2") (pin "21") (pinfunction "DATA5_21") (pintype "bidirectional"))
      (node (ref "IC2") (pin "22") (pinfunction "DATA4_22") (pintype "bidirectional"))
      (node (ref "IC2") (pin "23") (pinfunction "DATA3_23") (pintype "bidirectional"))
      (node (ref "IC2") (pin "24") (pinfunction "DATA2_24") (pintype "bidirectional"))
      (node (ref "IC2") (pin "25") (pinfunction "DATA1_25") (pintype "bidirectional"))
      (node (ref "IC2") (pin "26") (pinfunction "DATA0_26") (pintype "bidirectional"))
      (node (ref "IC2") (pin "32") (pinfunction "GNDD3_32") (pintype "bidirectional"))
      (node (ref "IC2") (pin "34") (pinfunction "TEST_MODE3_34") (pintype "bidirectional"))
      (node (ref "IC2") (pin "35") (pinfunction "TEST_MODE2_35") (pintype "bidirectional"))
      (node (ref "IC2") (pin "36") (pinfunction "TEST_MODE1_36") (pintype "bidirectional"))
      (node (ref "IC2") (pin "37") (pinfunction "TEST_MODE0_37") (pintype "bidirectional"))
      (node (ref "IC2") (pin "38") (pinfunction "ADDR14_38") (pintype "bidirectional"))
      (node (ref "IC2") (pin "39") (pinfunction "ADDR13_39") (pintype "bidirectional"))
      (node (ref "IC2") (pin "4") (pinfunction "GNDA0_4") (pintype "bidirectional"))
      (node (ref "IC2") (pin "40") (pinfunction "ADDR12_40") (pintype "bidirectional"))
      (node (ref "IC2") (pin "41") (pinfunction "ADDR11_41") (pintype "bidirectional"))
      (node (ref "IC2") (pin "42") (pinfunction "ADDR10_42") (pintype "bidirectional"))
      (node (ref "IC2") (pin "43") (pinfunction "GNDD4_43") (pintype "bidirectional"))
      (node (ref "IC2") (pin "45") (pinfunction "ADDR9_45") (pintype "bidirectional"))
      (node (ref "IC2") (pin "46") (pinfunction "ADDR8_46") (pintype "bidirectional"))
      (node (ref "IC2") (pin "47") (pinfunction "ADDR7_47") (pintype "bidirectional"))
      (node (ref "IC2") (pin "48") (pinfunction "ADDR6_48") (pintype "bidirectional"))
      (node (ref "IC2") (pin "49") (pinfunction "ADDR5_49") (pintype "bidirectional"))
      (node (ref "IC2") (pin "50") (pinfunction "ADDR4_50") (pintype "bidirectional"))
      (node (ref "IC2") (pin "51") (pinfunction "ADDR3_51") (pintype "bidirectional"))
      (node (ref "IC2") (pin "52") (pinfunction "ADDR2_52") (pintype "bidirectional"))
      (node (ref "IC2") (pin "53") (pinfunction "ADDR1_53") (pintype "bidirectional"))
      (node (ref "IC2") (pin "54") (pinfunction "ADDR0_54") (pintype "bidirectional"))
      (node (ref "IC2") (pin "63") (pinfunction "OPMODE0_63") (pintype "bidirectional"))
      (node (ref "IC2") (pin "64") (pinfunction "OPMODE1_64") (pintype "bidirectional"))
      (node (ref "IC2") (pin "65") (pinfunction "OPMODE2_65") (pintype "bidirectional"))
      (node (ref "IC2") (pin "68") (pinfunction "GNDD5_68") (pintype "bidirectional"))
      (node (ref "IC2") (pin "77") (pinfunction "GNDA2_77") (pintype "bidirectional"))
      (node (ref "IC3") (pin "2") (pinfunction "GND_2") (pintype "power_in"))
      (node (ref "J1") (pin "GND1") (pinfunction "6_GND1") (pintype "power_in"))
      (node (ref "J1") (pin "GND2") (pinfunction "4_GND2") (pintype "power_in"))
      (node (ref "J2") (pin "GND1") (pinfunction "6_GND1") (pintype "power_in"))
      (node (ref "J2") (pin "GND2") (pinfunction "4_GND2") (pintype "power_in"))
      (node (ref "J3") (pin "GND1") (pinfunction "6_GND1") (pintype "power_in"))
      (node (ref "J3") (pin "GND2") (pinfunction "4_GND2") (pintype "power_in"))
      (node (ref "J4") (pin "GND1") (pinfunction "6_GND1") (pintype "power_in"))
      (node (ref "J4") (pin "GND2") (pinfunction "4_GND2") (pintype "power_in"))
      (node (ref "J5") (pin "GND1") (pinfunction "6_GND1") (pintype "power_in"))
      (node (ref "J5") (pin "GND2") (pinfunction "4_GND2") (pintype "power_in"))
      (node (ref "J7") (pin "GND1") (pinfunction "6_GND1") (pintype "power_in"))
      (node (ref "J7") (pin "GND2") (pinfunction "4_GND2") (pintype "power_in"))
      (node (ref "JP5") (pin "4") (pinfunction "4_4") (pintype "passive"))
      (node (ref "LED10") (pin "K") (pinfunction "C_K") (pintype "passive"))
      (node (ref "LED14") (pin "K") (pinfunction "C_K") (pintype "passive"))
      (node (ref "LED3") (pin "K") (pinfunction "C_K") (pintype "passive"))
      (node (ref "LED4") (pin "K") (pinfunction "C_K") (pintype "passive"))
      (node (ref "LED9") (pin "K") (pinfunction "C_K") (pintype "passive"))
      (node (ref "Q1") (pin "3") (pinfunction "S_3") (pintype "passive"))
      (node (ref "Q2") (pin "3") (pinfunction "S_3") (pintype "passive"))
      (node (ref "Q3") (pin "2") (pinfunction "S_2") (pintype "passive"))
      (node (ref "Q4") (pin "3") (pinfunction "S_3") (pintype "passive"))
      (node (ref "Q5") (pin "3") (pinfunction "S_3") (pintype "passive"))
      (node (ref "Q6") (pin "3") (pinfunction "S_3") (pintype "passive"))
      (node (ref "R3") (pin "1") (pinfunction "1_1") (pintype "passive"))
      (node (ref "R30") (pin "1") (pinfunction "1_1") (pintype "passive"))
      (node (ref "RESET1") (pin "4") (pinfunction "4_4") (pintype "passive"))
      (node (ref "SERIAL") (pin "2") (pinfunction "C_2") (pintype "passive"))
      (node (ref "SG1") (pin "-") (pinfunction "2_-") (pintype "passive"))
      (node (ref "U$1") (pin "VSS") (pinfunction "GND_VSS") (pintype "bidirectional"))
      (node (ref "U$4") (pin "15") (pinfunction "GND_15") (pintype "bidirectional"))
      (node (ref "U$4") (pin "23") (pinfunction "GND1_23") (pintype "bidirectional"))
      (node (ref "U$4") (pin "35") (pinfunction "GND2_35") (pintype "bidirectional"))
      (node (ref "U$4") (pin "43") (pinfunction "GND3_43") (pintype "bidirectional"))
      (node (ref "U$4") (pin "5") (pinfunction "UGND_5") (pintype "bidirectional"))
      (node (ref "U$6") (pin "GND1") (pinfunction "GND1_GND1") (pintype "input"))
      (node (ref "U$6") (pin "GND2") (pinfunction "GND2_GND2") (pintype "input"))
      (node (ref "USB") (pin "2") (pinfunction "C_2") (pintype "passive"))
      (node (ref "X4") (pin "5") (pinfunction "5_5") (pintype "input"))
    )
    (net (code "57") (name "Net-(C23-Pad1)") (class "Default")
      (node (ref "C23") (pin "1") (pinfunction "1_1") (pintype "passive"))
      (node (ref "R20") (pin "1") (pinfunction "1_1") (pintype "passive"))
      (node (ref "R21") (pin "1") (pinfunction "1_1") (pintype "passive"))
    )
    (net (code "58") (name "Net-(C24-Pad1)") (class "Default")
      (node (ref "C24") (pin "1") (pinfunction "1_1") (pintype "passive"))
      (node (ref "R22") (pin "1") (pinfunction "1_1") (pintype "passive"))
      (node (ref "R23") (pin "1") (pinfunction "1_1") (pintype "passive"))
    )
    (net (code "59") (name "Net-(ETHERNET-G-)") (class "Default")
      (node (ref "ETHERNET") (pin "P$12") (pinfunction "G-_P$12") (pintype "bidirectional"))
      (node (ref "R2") (pin "1") (pinfunction "1_1") (pintype "passive"))
    )
    (net (code "60") (name "Net-(ETHERNET-Y-)") (class "Default")
      (node (ref "ETHERNET") (pin "P$13") (pinfunction "Y-_P$13") (pintype "bidirectional"))
      (node (ref "R19") (pin "1") (pinfunction "1_1") (pintype "passive"))
    )
    (net (code "61") (name "Net-(F1-Pad1)") (class "Default")
      (node (ref "F1") (pin "1") (pinfunction "1_1") (pintype "passive"))
      (node (ref "U$6") (pin "+12V") (pinfunction "+12V_+12V") (pintype "power_in"))
    )
    (net (code "62") (name "Net-(F2-Pad1)") (class "Default")
      (node (ref "F2") (pin "1") (pinfunction "1_1") (pintype "passive"))
      (node (ref "U$6") (pin "+5V") (pinfunction "+5V_+5V") (pintype "power_in"))
    )
    (net (code "63") (name "Net-(FDX-AG)") (class "Default")
      (node (ref "FDX") (pin "1") (pinfunction "AG_1") (pintype "passive"))
      (node (ref "RL9") (pin "2") (pinfunction "2_2") (pintype "passive"))
    )
    (net (code "64") (name "Net-(FDX-AR)") (class "Default")
      (node (ref "FDX") (pin "3") (pinfunction "AR_3") (pintype "passive"))
      (node (ref "RL8") (pin "2") (pinfunction "2_2") (pintype "passive"))
    )
    (net (code "65") (name "Net-(I2C_INT0-2)") (class "Default")
      (node (ref "I2C_INT0") (pin "SCL") (pinfunction "2_SCL") (pintype "bidirectional"))
      (node (ref "R11") (pin "1") (pinfunction "1_1") (pintype "passive"))
    )
    (net (code "66") (name "Net-(I2C_INT0-3)") (class "Default")
      (node (ref "I2C_INT0") (pin "SDA") (pinfunction "3_SDA") (pintype "bidirectional"))
      (node (ref "R8") (pin "1") (pinfunction "1_1") (pintype "passive"))
    )
    (net (code "67") (name "Net-(IC2-RSET_BG)") (class "Default")
      (node (ref "IC2") (pin "1") (pinfunction "RSET_BG_1") (pintype "bidirectional"))
      (node (ref "R30") (pin "2") (pinfunction "2_2") (pintype "passive"))
    )
    (net (code "68") (name "Net-(IC2-XTLN)") (class "Default")
      (node (ref "C31") (pin "1") (pinfunction "1_1") (pintype "passive"))
      (node (ref "IC2") (pin "75") (pinfunction "XTLN_75") (pintype "bidirectional"))
      (node (ref "R29") (pin "2") (pinfunction "2_2") (pintype "passive"))
      (node (ref "X1") (pin "P$2") (pinfunction "P$2_P$2") (pintype "bidirectional"))
    )
    (net (code "69") (name "Net-(IC2-XTLP)") (class "Default")
      (node (ref "C22") (pin "1") (pinfunction "1_1") (pintype "passive"))
      (node (ref "IC2") (pin "76") (pinfunction "XTLP_76") (pintype "bidirectional"))
      (node (ref "R29") (pin "1") (pinfunction "1_1") (pintype "passive"))
      (node (ref "X1") (pin "P$1") (pinfunction "P$1_P$1") (pintype "bidirectional"))
    )
    (net (code "70") (name "Net-(IC2-{slash}CS)") (class "Default")
      (node (ref "IC2") (pin "55") (pinfunction "/CS_55") (pintype "bidirectional"))
      (node (ref "IC2") (pin "57") (pinfunction "/WR_57") (pintype "bidirectional"))
      (node (ref "IC2") (pin "58") (pinfunction "/RD_58") (pintype "bidirectional"))
      (node (ref "R28") (pin "1") (pinfunction "1_1") (pintype "passive"))
    )
    (net (code "71") (name "Net-(J1-2)") (class "Default")
      (node (ref "J1") (pin "PWM") (pinfunction "2_PWM") (pintype "bidirectional"))
      (node (ref "LED5") (pin "K") (pinfunction "C_K") (pintype "passive"))
      (node (ref "Q2") (pin "2") (pinfunction "D_2") (pintype "passive"))
    )
    (net (code "72") (name "Net-(J1-3)") (class "Default")
      (node (ref "J1") (pin "I/O") (pinfunction "3_I/O") (pintype "bidirectional"))
      (node (ref "R32") (pin "2") (pinfunction "2_2") (pintype "passive"))
    )
    (net (code "73") (name "Net-(J2-2)") (class "Default")
      (node (ref "J2") (pin "PWM") (pinfunction "2_PWM") (pintype "bidirectional"))
      (node (ref "LED6") (pin "K") (pinfunction "C_K") (pintype "passive"))
      (node (ref "Q4") (pin "2") (pinfunction "D_2") (pintype "passive"))
    )
    (net (code "74") (name "Net-(J2-3)") (class "Default")
      (node (ref "J2") (pin "I/O") (pinfunction "3_I/O") (pintype "bidirectional"))
      (node (ref "R33") (pin "2") (pinfunction "2_2") (pintype "passive"))
    )
    (net (code "75") (name "Net-(J3-2)") (class "Default")
      (node (ref "J3") (pin "PWM") (pinfunction "2_PWM") (pintype "bidirectional"))
      (node (ref "LED7") (pin "K") (pinfunction "C_K") (pintype "passive"))
      (node (ref "Q5") (pin "2") (pinfunction "D_2") (pintype "passive"))
    )
    (net (code "76") (name "Net-(J3-3)") (class "Default")
      (node (ref "J3") (pin "I/O") (pinfunction "3_I/O") (pintype "bidirectional"))
      (node (ref "R34") (pin "2") (pinfunction "2_2") (pintype "passive"))
    )
    (net (code "77") (name "Net-(J4-2)") (class "Default")
      (node (ref "J4") (pin "PWM") (pinfunction "2_PWM") (pintype "bidirectional"))
      (node (ref "LED8") (pin "K") (pinfunction "C_K") (pintype "passive"))
      (node (ref "Q6") (pin "2") (pinfunction "D_2") (pintype "passive"))
    )
    (net (code "78") (name "Net-(J4-3)") (class "Default")
      (node (ref "J4") (pin "I/O") (pinfunction "3_I/O") (pintype "bidirectional"))
      (node (ref "R35") (pin "2") (pinfunction "2_2") (pintype "passive"))
    )
    (net (code "79") (name "Net-(J5-2)") (class "Default")
      (node (ref "J5") (pin "RX") (pinfunction "2_RX") (pintype "bidirectional"))
      (node (ref "R10") (pin "1") (pinfunction "1_1") (pintype "passive"))
    )
    (net (code "80") (name "Net-(J5-3)") (class "Default")
      (node (ref "J5") (pin "TX") (pinfunction "3_TX") (pintype "bidirectional"))
      (node (ref "R9") (pin "1") (pinfunction "1_1") (pintype "passive"))
    )
    (net (code "81") (name "Net-(J7-2)") (class "Default")
      (node (ref "J7") (pin "PWM") (pinfunction "2_PWM") (pintype "bidirectional"))
      (node (ref "LED2") (pin "K") (pinfunction "C_K") (pintype "passive"))
      (node (ref "Q1") (pin "2") (pinfunction "D_2") (pintype "passive"))
    )
    (net (code "82") (name "Net-(J7-3)") (class "Default")
      (node (ref "J7") (pin "I/O") (pinfunction "3_I/O") (pintype "bidirectional"))
      (node (ref "R") (pin "2") (pinfunction "2_2") (pintype "passive"))
    )
    (net (code "83") (name "Net-(LED2-PadA)") (class "Default")
      (node (ref "LED2") (pin "A") (pinfunction "A_A") (pintype "passive"))
      (node (ref "R25") (pin "1") (pinfunction "1_1") (pintype "passive"))
    )
    (net (code "84") (name "Net-(LED3-PadA)") (class "Default")
      (node (ref "LED3") (pin "A") (pinfunction "A_A") (pintype "passive"))
      (node (ref "R27") (pin "1") (pinfunction "1_1") (pintype "passive"))
    )
    (net (code "85") (name "Net-(LED4-PadA)") (class "Default")
      (node (ref "LED4") (pin "A") (pinfunction "A_A") (pintype "passive"))
      (node (ref "RL4") (pin "2") (pinfunction "2_2") (pintype "passive"))
    )
    (net (code "86") (name "Net-(LED5-PadA)") (class "Default")
      (node (ref "LED5") (pin "A") (pinfunction "A_A") (pintype "passive"))
      (node (ref "R4") (pin "1") (pinfunction "1_1") (pintype "passive"))
    )
    (net (code "87") (name "Net-(LED6-PadA)") (class "Default")
      (node (ref "LED6") (pin "A") (pinfunction "A_A") (pintype "passive"))
      (node (ref "R5") (pin "1") (pinfunction "1_1") (pintype "passive"))
    )
    (net (code "88") (name "Net-(LED7-PadA)") (class "Default")
      (node (ref "LED7") (pin "A") (pinfunction "A_A") (pintype "passive"))
      (node (ref "R6") (pin "1") (pinfunction "1_1") (pintype "passive"))
    )
    (net (code "89") (name "Net-(LED8-PadA)") (class "Default")
      (node (ref "LED8") (pin "A") (pinfunction "A_A") (pintype "passive"))
      (node (ref "R7") (pin "1") (pinfunction "1_1") (pintype "passive"))
    )
    (net (code "90") (name "Net-(LED9-PadA)") (class "Default")
      (node (ref "LED9") (pin "A") (pinfunction "A_A") (pintype "passive"))
      (node (ref "RL2") (pin "1") (pinfunction "1_1") (pintype "passive"))
    )
    (net (code "91") (name "Net-(LED10-PadA)") (class "Default")
      (node (ref "LED10") (pin "A") (pinfunction "A_A") (pintype "passive"))
      (node (ref "RL3") (pin "1") (pinfunction "1_1") (pintype "passive"))
    )
    (net (code "92") (name "Net-(LED14-PadA)") (class "Default")
      (node (ref "LED14") (pin "A") (pinfunction "A_A") (pintype "passive"))
      (node (ref "RL11") (pin "2") (pinfunction "2_2") (pintype "passive"))
    )
    (net (code "93") (name "Net-(R18-Pad2)") (class "Default")
      (node (ref "R18") (pin "2") (pinfunction "2_2") (pintype "passive"))
      (node (ref "U$1") (pin "SCK") (pinfunction "SCK_SCK") (pintype "bidirectional"))
    )
    (net (code "94") (name "Net-(R24-Pad2)") (class "Default")
      (node (ref "R24") (pin "2") (pinfunction "2_2") (pintype "passive"))
      (node (ref "X4") (pin "3") (pinfunction "3_3") (pintype "input"))
    )
    (net (code "95") (name "Net-(R31-Pad2)") (class "Default")
      (node (ref "R31") (pin "2") (pinfunction "2_2") (pintype "passive"))
      (node (ref "X4") (pin "2") (pinfunction "2_2") (pintype "input"))
    )
    (net (code "96") (name "Net-(SERIAL-AG)") (class "Default")
      (node (ref "RL6") (pin "2") (pinfunction "2_2") (pintype "passive"))
      (node (ref "SERIAL") (pin "1") (pinfunction "AG_1") (pintype "passive"))
    )
    (net (code "97") (name "Net-(SERIAL-AR)") (class "Default")
      (node (ref "RL5") (pin "2") (pinfunction "2_2") (pintype "passive"))
      (node (ref "SERIAL") (pin "3") (pinfunction "AR_3") (pintype "passive"))
    )
    (net (code "98") (name "Net-(U$1-CS)") (class "Default")
      (node (ref "R16") (pin "1") (pinfunction "1_1") (pintype "passive"))
      (node (ref "R17") (pin "1") (pinfunction "1_1") (pintype "passive"))
      (node (ref "U$1") (pin "CE") (pinfunction "CS_CE") (pintype "bidirectional"))
    )
    (net (code "99") (name "Net-(U$4-UCAP)") (class "Default")
      (node (ref "C3") (pin "2") (pinfunction "2_2") (pintype "passive"))
      (node (ref "U$4") (pin "6") (pinfunction "UCAP_6") (pintype "bidirectional"))
    )
    (net (code "100") (name "Net-(USB-AG)") (class "Default")
      (node (ref "RL7") (pin "2") (pinfunction "2_2") (pintype "passive"))
      (node (ref "USB") (pin "1") (pinfunction "AG_1") (pintype "passive"))
    )
    (net (code "101") (name "Net-(USB-AR)") (class "Default")
      (node (ref "RL1") (pin "2") (pinfunction "2_2") (pintype "passive"))
      (node (ref "USB") (pin "3") (pinfunction "AR_3") (pintype "passive"))
    )
    (net (code "102") (name "VUSB") (class "Default")
      (node (ref "C7") (pin "2") (pinfunction "2_2") (pintype "passive"))
      (node (ref "D4") (pin "A") (pinfunction "A_A") (pintype "passive"))
      (node (ref "U$4") (pin "7") (pinfunction "VBUS_7") (pintype "bidirectional"))
      (node (ref "X4") (pin "1") (pinfunction "1_1") (pintype "input"))
    )
    (net (code "103") (name "unconnected-(IC2-NC0-Pad3)") (class "Default")
      (node (ref "IC2") (pin "3") (pinfunction "NC0_3") (pintype "bidirectional"))
    )
    (net (code "104") (name "unconnected-(IC2-NC1-Pad60)") (class "Default")
      (node (ref "IC2") (pin "60") (pinfunction "NC1_60") (pintype "bidirectional"))
    )
    (net (code "105") (name "unconnected-(IC2-NC2-Pad61)") (class "Default")
      (node (ref "IC2") (pin "61") (pinfunction "NC2_61") (pintype "bidirectional"))
    )
    (net (code "106") (name "unconnected-(IC2-NC3-Pad62)") (class "Default")
      (node (ref "IC2") (pin "62") (pinfunction "NC3_62") (pintype "bidirectional"))
    )
    (net (code "107") (name "unconnected-(IC2-NC4-Pad78)") (class "Default")
      (node (ref "IC2") (pin "78") (pinfunction "NC4_78") (pintype "bidirectional"))
    )
    (net (code "108") (name "unconnected-(IC2-NC5-Pad79)") (class "Default")
      (node (ref "IC2") (pin "79") (pinfunction "NC5_79") (pintype "bidirectional"))
    )
    (net (code "109") (name "unconnected-(IC2-NC6-Pad80)") (class "Default")
      (node (ref "IC2") (pin "80") (pinfunction "NC6_80") (pintype "bidirectional"))
    )
    (net (code "110") (name "unconnected-(Q1-D-Pad4)") (class "Default")
      (node (ref "Q1") (pin "4") (pinfunction "D_4") (pintype "passive"))
    )
    (net (code "111") (name "unconnected-(Q2-D-Pad4)") (class "Default")
      (node (ref "Q2") (pin "4") (pinfunction "D_4") (pintype "passive"))
    )
    (net (code "112") (name "unconnected-(Q4-D-Pad4)") (class "Default")
      (node (ref "Q4") (pin "4") (pinfunction "D_4") (pintype "passive"))
    )
    (net (code "113") (name "unconnected-(Q5-D-Pad4)") (class "Default")
      (node (ref "Q5") (pin "4") (pinfunction "D_4") (pintype "passive"))
    )
    (net (code "114") (name "unconnected-(Q6-D-Pad4)") (class "Default")
      (node (ref "Q6") (pin "4") (pinfunction "D_4") (pintype "passive"))
    )
    (net (code "115") (name "unconnected-(RESET1-Pad1)") (class "Default")
      (node (ref "RESET1") (pin "1") (pinfunction "1_1") (pintype "passive"))
    )
    (net (code "116") (name "unconnected-(RESET1-Pad3)") (class "Default")
      (node (ref "RESET1") (pin "3") (pinfunction "3_3") (pintype "passive"))
    )
    (net (code "117") (name "unconnected-(X4-Pad4)") (class "Default")
      (node (ref "X4") (pin "4") (pinfunction "4_4") (pintype "input"))
    )
  )
)
